# MEM.net
KiCad netlist of a schematic drawn in Altium Designer
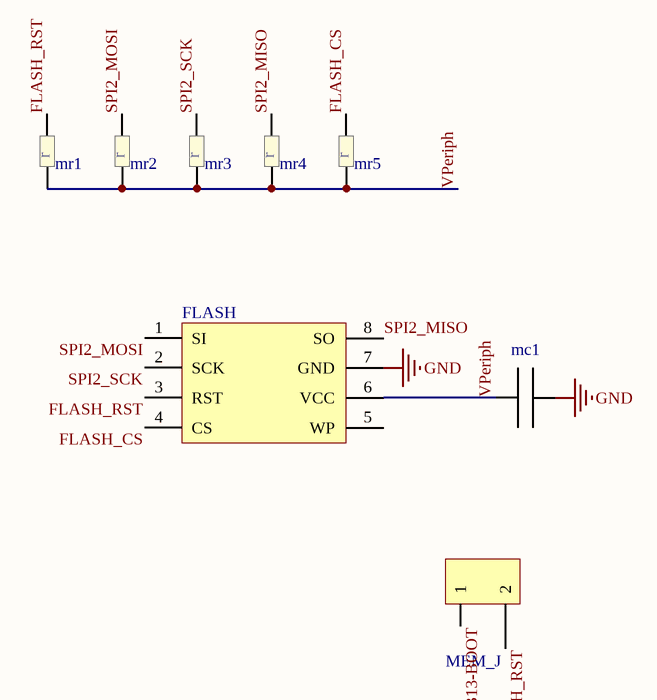
[diagram p0: MEM.SchDoc]

(export (version "E")
  (design (tool "Eeschema 10.0.6"))
  (components
    (comp (ref "FLASH")
      (value "SPI-FLASH")
      (footprint "abr_ic_spi_flash_3d")
      (libsource (lib "abr_ic") (part "abr_ic_at_45db161_e"))
    )
    (comp (ref "mc1")
      (value "100nf")
      (footprint "abr_cap_0805_3d")
      (libsource (lib "abr_smd_0805_all") (part "abr_cap_0805"))
    )
    (comp (ref "MEM_J")
      (value "pin header 2mm")
      (footprint "abr_ph_2x1_2mm_3d_male")
      (libsource (lib "abr_ph_2mm_96_02") (part "abr_2x1_2mm"))
    )
    (comp (ref "mr1")
      (value "10k")
      (footprint "abr_res_0805_3d")
      (libsource (lib "abr_smd_0805_all") (part "abr_res_0805"))
    )
    (comp (ref "mr2")
      (value "10k")
      (footprint "abr_res_0805_3d")
      (libsource (lib "abr_smd_0805_all") (part "abr_res_0805"))
    )
    (comp (ref "mr3")
      (value "10k")
      (footprint "abr_res_0805_3d")
      (libsource (lib "abr_smd_0805_all") (part "abr_res_0805"))
    )
    (comp (ref "mr4")
      (value "10k")
      (footprint "abr_res_0805_3d")
      (libsource (lib "abr_smd_0805_all") (part "abr_res_0805"))
    )
    (comp (ref "mr5")
      (value "10k")
      (footprint "abr_res_0805_3d")
      (libsource (lib "abr_smd_0805_all") (part "abr_res_0805"))
    )
  )
  (nets
    (net (code "1") (name "/FLASH_CS") (class "Default")
      (node (ref "FLASH") (pin "4") (pinfunction "CS_4") (pintype "passive"))
      (node (ref "mr5") (pin "1") (pinfunction "0_1") (pintype "passive"))
    )
    (net (code "2") (name "/FLASH_RST") (class "Default")
      (node (ref "FLASH") (pin "3") (pinfunction "RST_3") (pintype "passive"))
      (node (ref "MEM_J") (pin "2") (pinfunction "2_2") (pintype "passive"))
      (node (ref "mr1") (pin "1") (pinfunction "0_1") (pintype "passive"))
    )
    (net (code "3") (name "/PB13-BOOT") (class "Default")
      (node (ref "MEM_J") (pin "1") (pinfunction "1_1") (pintype "passive"))
    )
    (net (code "4") (name "/SPI2_MISO") (class "Default")
      (node (ref "FLASH") (pin "8") (pinfunction "SO_8") (pintype "passive"))
      (node (ref "mr4") (pin "1") (pinfunction "0_1") (pintype "passive"))
    )
    (net (code "5") (name "/SPI2_MOSI") (class "Default")
      (node (ref "FLASH") (pin "1") (pinfunction "SI_1") (pintype "passive"))
      (node (ref "mr2") (pin "1") (pinfunction "0_1") (pintype "passive"))
    )
    (net (code "6") (name "/SPI2_SCK") (class "Default")
      (node (ref "FLASH") (pin "2") (pinfunction "SCK_2") (pintype "passive"))
      (node (ref "mr3") (pin "1") (pinfunction "0_1") (pintype "passive"))
    )
    (net (code "7") (name "/VPeriph") (class "Default")
      (node (ref "FLASH") (pin "6") (pinfunction "VCC_6") (pintype "passive"))
      (node (ref "mc1") (pin "1") (pinfunction "10_1") (pintype "passive"))
      (node (ref "mr1") (pin "0") (pinfunction "0_0") (pintype "passive"))
      (node (ref "mr2") (pin "0") (pinfunction "0_0") (pintype "passive"))
      (node (ref "mr3") (pin "0") (pinfunction "0_0") (pintype "passive"))
      (node (ref "mr4") (pin "0") (pinfunction "0_0") (pintype "passive"))
      (node (ref "mr5") (pin "0") (pinfunction "0_0") (pintype "passive"))
    )
    (net (code "8") (name "GND") (class "Default")
      (node (ref "FLASH") (pin "7") (pinfunction "GND_7") (pintype "passive"))
      (node (ref "mc1") (pin "0") (pinfunction "2_0") (pintype "passive"))
    )
    (net (code "9") (name "unconnected-(FLASH-WP-Pad5)") (class "Default")
      (node (ref "FLASH") (pin "5") (pinfunction "WP_5") (pintype "passive"))
    )
  )
)
